# mcu.net
KiCad netlist of a schematic drawn in Altium Designer
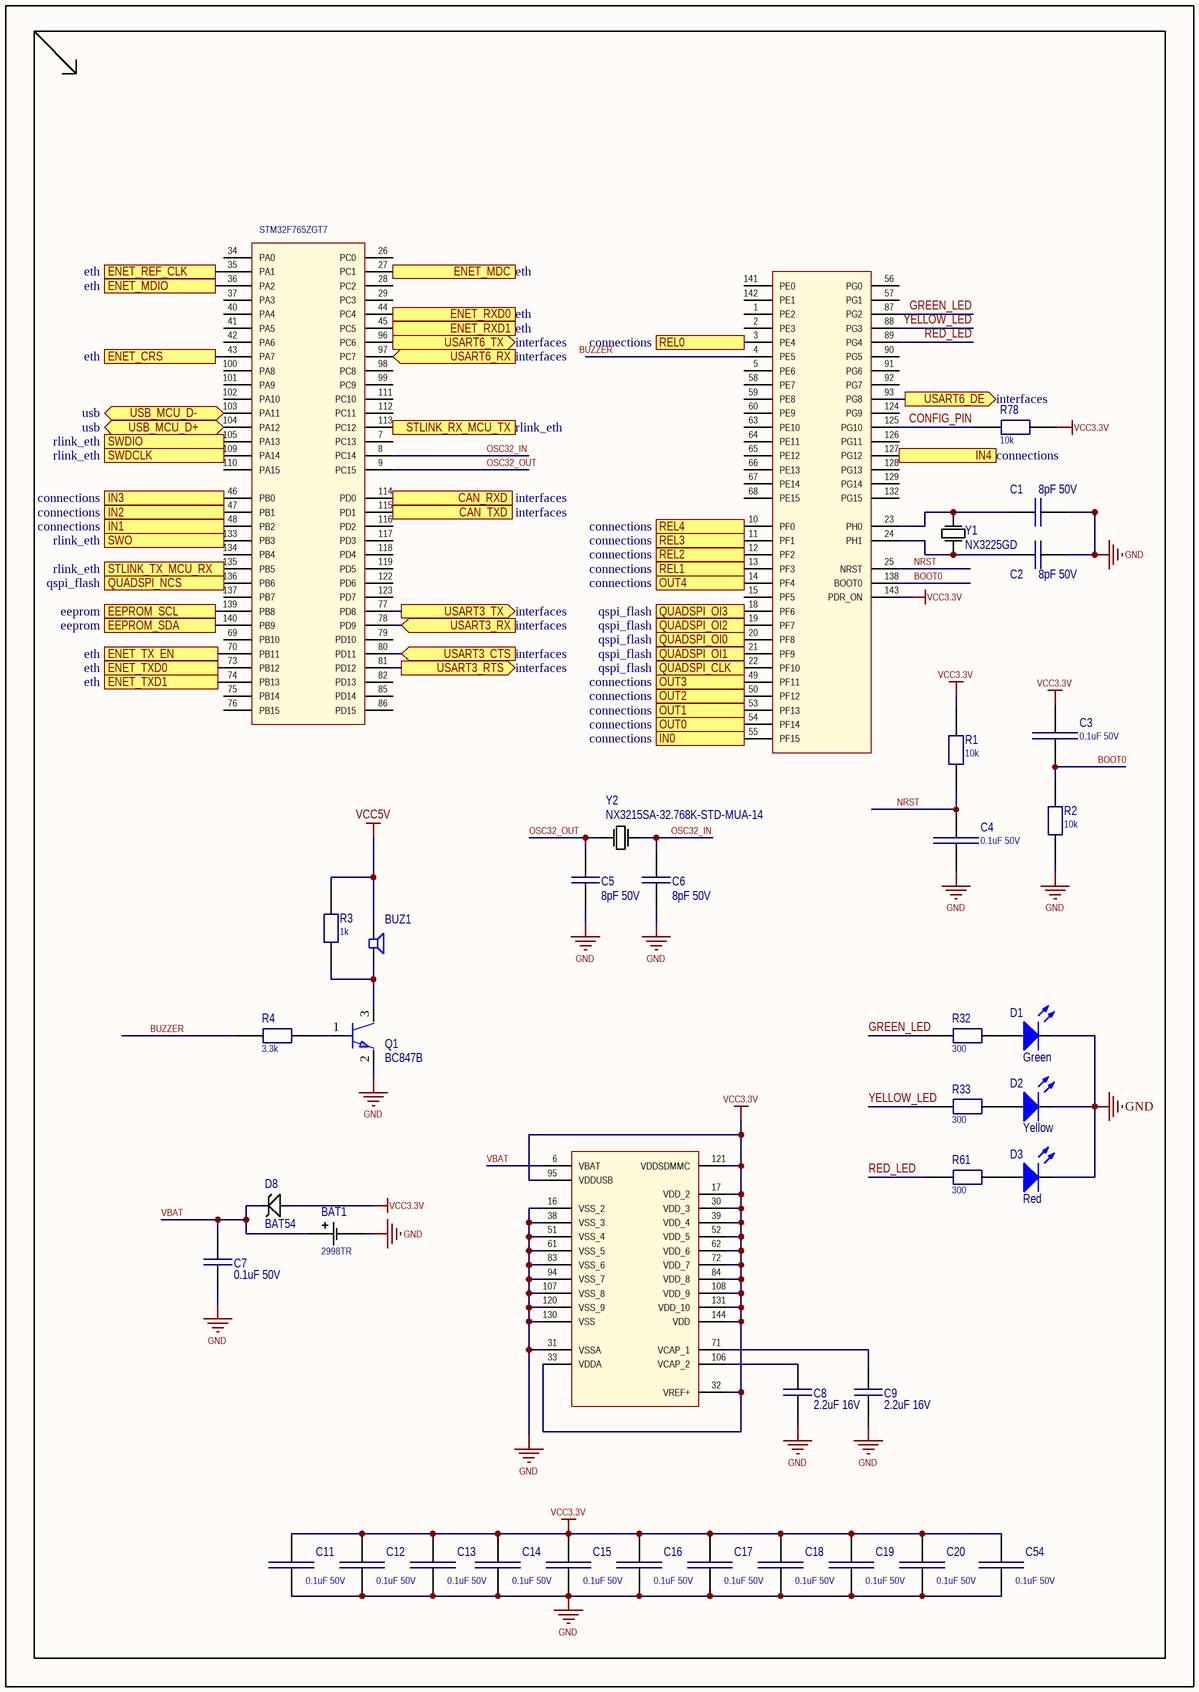
[diagram p0: mcu.SchDoc]

(export (version "E")
  (design (tool "Eeschema 10.0.6"))
  (components
    (comp (ref "BAT1")
      (value "2998TR")
      (footprint "BAT_2998TR")
      (description "Battery")
      (fields (field (name "JLCPCB PART") "C6078169"))
      (libsource (lib "battery_socets") (part "2998TR"))
    )
    (comp (ref "BUZ1")
      (value "~")
      (footprint "SPKR_PKMCS0909E4000-R1")
      (description "Piezoelectric Sounders")
      (fields (field (name "PART") "L-KLS3-SMT-09X1.8") (field (name "ALTERNATIVE PART") "PKMCS0909E4000-R1"))
      (libsource (lib "other") (part "BUZZER"))
    )
    (comp (ref "C1")
      (value "8pF 50V")
      (footprint "C_0603")
      (description "Capacitor")
      (fields (field (name "PART") "CC0603DRNPO9BN8R0") (field (name "JLCPCB PART") "C326970"))
      (libsource (lib "capacitors") (part "CAP_SMD"))
    )
    (comp (ref "C2")
      (value "8pF 50V")
      (footprint "C_0603")
      (description "Capacitor")
      (fields (field (name "PART") "CC0603DRNPO9BN8R0") (field (name "JLCPCB PART") "C326970"))
      (libsource (lib "capacitors") (part "CAP_SMD"))
    )
    (comp (ref "C3")
      (value "0.1uF 50V")
      (footprint "C_0603")
      (description "Capacitor")
      (fields (field (name "PART") "CC0603KPX7R9BB104") (field (name "JLCPCB PART") "C14663"))
      (libsource (lib "AX_Altium_v2.3") (part "C0603"))
    )
    (comp (ref "C4")
      (value "0.1uF 50V")
      (footprint "C_0603")
      (description "Capacitor")
      (fields (field (name "PART") "CC0603KPX7R9BB104") (field (name "JLCPCB PART") "C14663"))
      (libsource (lib "AX_Altium_v2.3") (part "C0603"))
    )
    (comp (ref "C5")
      (value "8pF 50V")
      (footprint "C_0603")
      (description "Capacitor")
      (fields (field (name "PART") "CC0603DRNPO9BN8R0") (field (name "JLCPCB PART") "C326970"))
      (libsource (lib "capacitors") (part "CAP_SMD"))
    )
    (comp (ref "C6")
      (value "8pF 50V")
      (footprint "C_0603")
      (description "Capacitor")
      (fields (field (name "PART") "CC0603DRNPO9BN8R0") (field (name "JLCPCB PART") "C326970"))
      (libsource (lib "capacitors") (part "CAP_SMD"))
    )
    (comp (ref "C7")
      (value "0.1uF 50V")
      (footprint "C_0603")
      (description "Capacitor")
      (fields (field (name "PART") "CC0603KPX7R9BB104") (field (name "JLCPCB PART") "C14663"))
      (libsource (lib "capacitors") (part "CAP_SMD"))
    )
    (comp (ref "C8")
      (value "2.2uF 16V")
      (footprint "C_0603")
      (description "Capacitor")
      (fields (field (name "PART") "CC0603KRX5R7BB225") (field (name "JLCPCB PART") "C106853"))
      (libsource (lib "capacitors") (part "CAP_SMD"))
    )
    (comp (ref "C9")
      (value "2.2uF 16V")
      (footprint "C_0603")
      (description "Capacitor")
      (fields (field (name "PART") "CC0603KRX5R7BB225") (field (name "JLCPCB PART") "C106853"))
      (libsource (lib "capacitors") (part "CAP_SMD"))
    )
    (comp (ref "C11")
      (value "0.1uF 50V")
      (footprint "C_0603")
      (description "Capacitor")
      (fields (field (name "PART") "CC0603KPX7R9BB104") (field (name "JLCPCB PART") "C14663"))
      (libsource (lib "AX_Altium_v2.3") (part "C0603"))
    )
    (comp (ref "C12")
      (value "0.1uF 50V")
      (footprint "C_0603")
      (description "Capacitor")
      (fields (field (name "PART") "CC0603KPX7R9BB104") (field (name "JLCPCB PART") "C14663"))
      (libsource (lib "AX_Altium_v2.3") (part "C0603"))
    )
    (comp (ref "C13")
      (value "0.1uF 50V")
      (footprint "C_0603")
      (description "Capacitor")
      (fields (field (name "PART") "CC0603KPX7R9BB104") (field (name "JLCPCB PART") "C14663"))
      (libsource (lib "AX_Altium_v2.3") (part "C0603"))
    )
    (comp (ref "C14")
      (value "0.1uF 50V")
      (footprint "C_0603")
      (description "Capacitor")
      (fields (field (name "PART") "CC0603KPX7R9BB104") (field (name "JLCPCB PART") "C14663"))
      (libsource (lib "AX_Altium_v2.3") (part "C0603"))
    )
    (comp (ref "C15")
      (value "0.1uF 50V")
      (footprint "C_0603")
      (description "Capacitor")
      (fields (field (name "PART") "CC0603KPX7R9BB104") (field (name "JLCPCB PART") "C14663"))
      (libsource (lib "AX_Altium_v2.3") (part "C0603"))
    )
    (comp (ref "C16")
      (value "0.1uF 50V")
      (footprint "C_0603")
      (description "Capacitor")
      (fields (field (name "PART") "CC0603KPX7R9BB104") (field (name "JLCPCB PART") "C14663"))
      (libsource (lib "AX_Altium_v2.3") (part "C0603"))
    )
    (comp (ref "C17")
      (value "0.1uF 50V")
      (footprint "C_0603")
      (description "Capacitor")
      (fields (field (name "PART") "CC0603KPX7R9BB104") (field (name "JLCPCB PART") "C14663"))
      (libsource (lib "AX_Altium_v2.3") (part "C0603"))
    )
    (comp (ref "C18")
      (value "0.1uF 50V")
      (footprint "C_0603")
      (description "Capacitor")
      (fields (field (name "PART") "CC0603KPX7R9BB104") (field (name "JLCPCB PART") "C14663"))
      (libsource (lib "AX_Altium_v2.3") (part "C0603"))
    )
    (comp (ref "C19")
      (value "0.1uF 50V")
      (footprint "C_0603")
      (description "Capacitor")
      (fields (field (name "PART") "CC0603KPX7R9BB104") (field (name "JLCPCB PART") "C14663"))
      (libsource (lib "AX_Altium_v2.3") (part "C0603"))
    )
    (comp (ref "C20")
      (value "0.1uF 50V")
      (footprint "C_0603")
      (description "Capacitor")
      (fields (field (name "PART") "CC0603KPX7R9BB104") (field (name "JLCPCB PART") "C14663"))
      (libsource (lib "AX_Altium_v2.3") (part "C0603"))
    )
    (comp (ref "C54")
      (value "0.1uF 50V")
      (footprint "C_0603")
      (description "Capacitor")
      (fields (field (name "PART") "CC0603KPX7R9BB104") (field (name "JLCPCB PART") "C14663"))
      (libsource (lib "AX_Altium_v2.3") (part "C0603"))
    )
    (comp (ref "D1")
      (value "Green")
      (footprint "LED_0603")
      (description "LED")
      (fields (field (name "PART") "FYLS-0603PGC") (field (name "ALTERNATIVE PART") "KP-1608CGCK"))
      (libsource (lib "led_lcd") (part "LED_SMT_0603"))
    )
    (comp (ref "D2")
      (value "Yellow")
      (footprint "LED_0603")
      (description "LED")
      (fields (field (name "PART") "FYLS-0603PGC") (field (name "ALTERNATIVE PART") "KP-1608CGCK"))
      (libsource (lib "led_lcd") (part "LED_SMT_0603"))
    )
    (comp (ref "D3")
      (value "Red")
      (footprint "LED_0603")
      (description "LED")
      (fields (field (name "PART") "FYLS-0603PGC") (field (name "ALTERNATIVE PART") "KP-1608CGCK"))
      (libsource (lib "led_lcd") (part "LED_SMT_0603"))
    )
    (comp (ref "D8")
      (value "BAT54")
      (footprint "SOT23")
      (description "Diode")
      (fields (field (name "JLCPCB PART") "C408389"))
      (libsource (lib "diode") (part "BAT54"))
    )
    (comp (ref "Q1")
      (value "BC847B")
      (footprint "SOT23")
      (description "Transistor")
      (fields (field (name "JLCPCB PART") "C181140"))
      (libsource (lib "AX_Altium_v2.3") (part "BC847B"))
    )
    (comp (ref "R1")
      (value "10k")
      (footprint "R_0603")
      (description "Resistor")
      (fields (field (name "PART") "RC0603JR-0710KL") (field (name "JLCPCB PART") "C99198"))
      (libsource (lib "resistors") (part "RES_SMD"))
    )
    (comp (ref "R2")
      (value "10k")
      (footprint "R_0603")
      (description "Resistor")
      (fields (field (name "PART") "RC0603JR-0710KL") (field (name "JLCPCB PART") "C99198"))
      (libsource (lib "resistors") (part "RES_SMD"))
    )
    (comp (ref "R3")
      (value "1k")
      (footprint "R_0603")
      (description "Resistor")
      (fields (field (name "PART") "RC0603FR-071KL") (field (name "JLCPCB PART") "C22548"))
      (libsource (lib "resistors") (part "RES_SMD"))
    )
    (comp (ref "R4")
      (value "3.3k")
      (footprint "R_0603")
      (description "Resistor")
      (fields (field (name "PART") "RC0603FR-073K3L") (field (name "JLCPCB PART") "C108078"))
      (libsource (lib "resistors") (part "RES_SMD"))
    )
    (comp (ref "R32")
      (value "300")
      (footprint "R_0603")
      (description "Resistor")
      (fields (field (name "PART") "RC0603FR-07300RL") (field (name "JLCPCB PART") "C114617"))
      (libsource (lib "resistors") (part "R0603"))
    )
    (comp (ref "R33")
      (value "300")
      (footprint "R_0603")
      (description "Resistor")
      (fields (field (name "PART") "RC0603FR-07300RL") (field (name "JLCPCB PART") "C114617"))
      (libsource (lib "resistors") (part "R0603"))
    )
    (comp (ref "R61")
      (value "300")
      (footprint "R_0603")
      (description "Resistor")
      (fields (field (name "PART") "RC0603FR-07300RL") (field (name "JLCPCB PART") "C114617"))
      (libsource (lib "resistors") (part "R0603"))
    )
    (comp (ref "R78")
      (value "10k")
      (footprint "R_0603")
      (description "Resistor")
      (fields (field (name "PART") "RC0603JR-0710KL") (field (name "JLCPCB PART") "C99198"))
      (libsource (lib "resistors") (part "RES_SMD"))
    )
    (comp (ref "U1")
      (value "STM32F765ZGT7")
      (footprint "TQFP144_M")
      (description "Microcontroller")
      (fields
        (field (name "MANUFACTURER_PART_NUMBER") "STM32F76XZXT")
        (field (name "PART") "STM32F765ZGT")
        (field (name "COPYRIGHT") "Copyright (C) 2016 Accelerated Designs. All rights reserved")
      )
      (libsource (lib "STM32 F4") (part "STM32F76XZXT"))
    )
    (comp (ref "Y1")
      (value "NX3225GD")
      (footprint "NX3225GD")
      (description "Crystal Oscillator")
      (fields (field (name "PART") "NX3225GD-8MHZ-STD-CRA-3") (field (name "JLCPCB PART") "C889706"))
      (libsource (lib "crystals_oscillators") (part "NX3225GD"))
    )
    (comp (ref "Y2")
      (value "NX3215SA-32.768K-STD-MUA-14")
      (footprint "XTAL_NX3215SA-32.768K-STD-MUA-8")
      (description "Crystal Oscillator")
      (fields (field (name "JLCPCB PART") "C156244"))
      (libsource (lib "crystals_oscillators") (part "NX3215SA-32.768K"))
    )
  )
  (nets
    (net (code "1") (name "/BOOT0") (class "Default")
      (node (ref "C3") (pin "2") (pinfunction "2_2") (pintype "passive"))
      (node (ref "R2") (pin "2") (pinfunction "2_2") (pintype "passive"))
      (node (ref "U1") (pin "138") (pinfunction "BOOT0_138") (pintype "passive"))
    )
    (net (code "2") (name "/BUZZER") (class "Default")
      (node (ref "R4") (pin "1") (pinfunction "1_1") (pintype "passive"))
      (node (ref "U1") (pin "4") (pinfunction "PE5_4") (pintype "passive"))
    )
    (net (code "3") (name "/CAN_RXD") (class "Default")
      (node (ref "U1") (pin "114") (pinfunction "PD0_114") (pintype "passive"))
    )
    (net (code "4") (name "/CAN_TXD") (class "Default")
      (node (ref "U1") (pin "115") (pinfunction "PD1_115") (pintype "passive"))
    )
    (net (code "5") (name "/CONFIG_PIN") (class "Default")
      (node (ref "R78") (pin "1") (pinfunction "1_1") (pintype "passive"))
      (node (ref "U1") (pin "125") (pinfunction "PG10_125") (pintype "passive"))
    )
    (net (code "6") (name "/EEPROM_SCL") (class "Default")
      (node (ref "U1") (pin "139") (pinfunction "PB8_139") (pintype "passive"))
    )
    (net (code "7") (name "/EEPROM_SDA") (class "Default")
      (node (ref "U1") (pin "140") (pinfunction "PB9_140") (pintype "passive"))
    )
    (net (code "8") (name "/ENET_CRS") (class "Default")
      (node (ref "U1") (pin "43") (pinfunction "PA7_43") (pintype "passive"))
    )
    (net (code "9") (name "/ENET_MDC") (class "Default")
      (node (ref "U1") (pin "27") (pinfunction "PC1_27") (pintype "passive"))
    )
    (net (code "10") (name "/ENET_MDIO") (class "Default")
      (node (ref "U1") (pin "36") (pinfunction "PA2_36") (pintype "passive"))
    )
    (net (code "11") (name "/ENET_REF_CLK") (class "Default")
      (node (ref "U1") (pin "35") (pinfunction "PA1_35") (pintype "passive"))
    )
    (net (code "12") (name "/ENET_RXD0") (class "Default")
      (node (ref "U1") (pin "44") (pinfunction "PC4_44") (pintype "passive"))
    )
    (net (code "13") (name "/ENET_RXD1") (class "Default")
      (node (ref "U1") (pin "45") (pinfunction "PC5_45") (pintype "passive"))
    )
    (net (code "14") (name "/ENET_TXD0") (class "Default")
      (node (ref "U1") (pin "73") (pinfunction "PB12_73") (pintype "passive"))
    )
    (net (code "15") (name "/ENET_TXD1") (class "Default")
      (node (ref "U1") (pin "74") (pinfunction "PB13_74") (pintype "passive"))
    )
    (net (code "16") (name "/ENET_TX_EN") (class "Default")
      (node (ref "U1") (pin "70") (pinfunction "PB11_70") (pintype "passive"))
    )
    (net (code "17") (name "/GREEN_LED") (class "Default")
      (node (ref "R32") (pin "2") (pinfunction "2_2") (pintype "passive"))
      (node (ref "U1") (pin "87") (pinfunction "PG2_87") (pintype "passive"))
    )
    (net (code "18") (name "/IN0") (class "Default")
      (node (ref "U1") (pin "55") (pinfunction "PF15_55") (pintype "passive"))
    )
    (net (code "19") (name "/IN1") (class "Default")
      (node (ref "U1") (pin "48") (pinfunction "PB2_48") (pintype "passive"))
    )
    (net (code "20") (name "/IN2") (class "Default")
      (node (ref "U1") (pin "47") (pinfunction "PB1_47") (pintype "passive"))
    )
    (net (code "21") (name "/IN3") (class "Default")
      (node (ref "U1") (pin "46") (pinfunction "PB0_46") (pintype "passive"))
    )
    (net (code "22") (name "/IN4") (class "Default")
      (node (ref "U1") (pin "127") (pinfunction "PG12_127") (pintype "passive"))
    )
    (net (code "23") (name "/NRST") (class "Default")
      (node (ref "C4") (pin "2") (pinfunction "2_2") (pintype "passive"))
      (node (ref "R1") (pin "1") (pinfunction "1_1") (pintype "passive"))
      (node (ref "U1") (pin "25") (pinfunction "NRST_25") (pintype "passive"))
    )
    (net (code "24") (name "/OSC32_IN") (class "Default")
      (node (ref "C6") (pin "2") (pinfunction "2_2") (pintype "passive"))
      (node (ref "U1") (pin "8") (pinfunction "PC14_8") (pintype "passive"))
      (node (ref "Y2") (pin "2") (pinfunction "OSC2_2") (pintype "passive"))
    )
    (net (code "25") (name "/OSC32_OUT") (class "Default")
      (node (ref "C5") (pin "2") (pinfunction "2_2") (pintype "passive"))
      (node (ref "U1") (pin "9") (pinfunction "PC15_9") (pintype "passive"))
      (node (ref "Y2") (pin "1") (pinfunction "OSC1_1") (pintype "passive"))
    )
    (net (code "26") (name "/OUT0") (class "Default")
      (node (ref "U1") (pin "54") (pinfunction "PF14_54") (pintype "passive"))
    )
    (net (code "27") (name "/OUT1") (class "Default")
      (node (ref "U1") (pin "53") (pinfunction "PF13_53") (pintype "passive"))
    )
    (net (code "28") (name "/OUT2") (class "Default")
      (node (ref "U1") (pin "50") (pinfunction "PF12_50") (pintype "passive"))
    )
    (net (code "29") (name "/OUT3") (class "Default")
      (node (ref "U1") (pin "49") (pinfunction "PF11_49") (pintype "passive"))
    )
    (net (code "30") (name "/OUT4") (class "Default")
      (node (ref "U1") (pin "14") (pinfunction "PF4_14") (pintype "passive"))
    )
    (net (code "31") (name "/QUADSPI_CLK") (class "Default")
      (node (ref "U1") (pin "22") (pinfunction "PF10_22") (pintype "passive"))
    )
    (net (code "32") (name "/QUADSPI_NCS") (class "Default")
      (node (ref "U1") (pin "136") (pinfunction "PB6_136") (pintype "passive"))
    )
    (net (code "33") (name "/QUADSPI_OI0") (class "Default")
      (node (ref "U1") (pin "20") (pinfunction "PF8_20") (pintype "passive"))
    )
    (net (code "34") (name "/QUADSPI_OI1") (class "Default")
      (node (ref "U1") (pin "21") (pinfunction "PF9_21") (pintype "passive"))
    )
    (net (code "35") (name "/QUADSPI_OI2") (class "Default")
      (node (ref "U1") (pin "19") (pinfunction "PF7_19") (pintype "passive"))
    )
    (net (code "36") (name "/QUADSPI_OI3") (class "Default")
      (node (ref "U1") (pin "18") (pinfunction "PF6_18") (pintype "passive"))
    )
    (net (code "37") (name "/RED_LED") (class "Default")
      (node (ref "R61") (pin "2") (pinfunction "2_2") (pintype "passive"))
      (node (ref "U1") (pin "89") (pinfunction "PG4_89") (pintype "passive"))
    )
    (net (code "38") (name "/REL0") (class "Default")
      (node (ref "U1") (pin "3") (pinfunction "PE4_3") (pintype "passive"))
    )
    (net (code "39") (name "/REL1") (class "Default")
      (node (ref "U1") (pin "13") (pinfunction "PF3_13") (pintype "passive"))
    )
    (net (code "40") (name "/REL2") (class "Default")
      (node (ref "U1") (pin "12") (pinfunction "PF2_12") (pintype "passive"))
    )
    (net (code "41") (name "/REL3") (class "Default")
      (node (ref "U1") (pin "11") (pinfunction "PF1_11") (pintype "passive"))
    )
    (net (code "42") (name "/REL4") (class "Default")
      (node (ref "U1") (pin "10") (pinfunction "PF0_10") (pintype "passive"))
    )
    (net (code "43") (name "/STLINK_RX_MCU_TX") (class "Default")
      (node (ref "U1") (pin "113") (pinfunction "PC12_113") (pintype "passive"))
    )
    (net (code "44") (name "/STLINK_TX_MCU_RX") (class "Default")
      (node (ref "U1") (pin "135") (pinfunction "PB5_135") (pintype "passive"))
    )
    (net (code "45") (name "/SWDCLK") (class "Default")
      (node (ref "U1") (pin "109") (pinfunction "PA14_109") (pintype "passive"))
    )
    (net (code "46") (name "/SWDIO") (class "Default")
      (node (ref "U1") (pin "105") (pinfunction "PA13_105") (pintype "passive"))
    )
    (net (code "47") (name "/SWO") (class "Default")
      (node (ref "U1") (pin "133") (pinfunction "PB3_133") (pintype "passive"))
    )
    (net (code "48") (name "/USART3_CTS") (class "Default")
      (node (ref "U1") (pin "80") (pinfunction "PD11_80") (pintype "passive"))
    )
    (net (code "49") (name "/USART3_RTS") (class "Default")
      (node (ref "U1") (pin "81") (pinfunction "PD12_81") (pintype "passive"))
    )
    (net (code "50") (name "/USART3_RX") (class "Default")
      (node (ref "U1") (pin "78") (pinfunction "PD9_78") (pintype "passive"))
    )
    (net (code "51") (name "/USART3_TX") (class "Default")
      (node (ref "U1") (pin "77") (pinfunction "PD8_77") (pintype "passive"))
    )
    (net (code "52") (name "/USART6_DE") (class "Default")
      (node (ref "U1") (pin "93") (pinfunction "PG8_93") (pintype "passive"))
    )
    (net (code "53") (name "/USART6_RX") (class "Default")
      (node (ref "U1") (pin "97") (pinfunction "PC7_97") (pintype "passive"))
    )
    (net (code "54") (name "/USART6_TX") (class "Default")
      (node (ref "U1") (pin "96") (pinfunction "PC6_96") (pintype "passive"))
    )
    (net (code "55") (name "/USB_MCU_D+") (class "Default")
      (node (ref "U1") (pin "104") (pinfunction "PA12_104") (pintype "passive"))
    )
    (net (code "56") (name "/USB_MCU_D-") (class "Default")
      (node (ref "U1") (pin "103") (pinfunction "PA11_103") (pintype "passive"))
    )
    (net (code "57") (name "/VBAT") (class "Default")
      (node (ref "BAT1") (pin "P1") (pinfunction "+_P1") (pintype "passive"))
      (node (ref "C7") (pin "2") (pinfunction "2_2") (pintype "passive"))
      (node (ref "D8") (pin "3") (pinfunction "3_3") (pintype "passive"))
      (node (ref "U1") (pin "6") (pinfunction "VBAT_6") (pintype "passive"))
    )
    (net (code "58") (name "/YELLOW_LED") (class "Default")
      (node (ref "R33") (pin "2") (pinfunction "2_2") (pintype "passive"))
      (node (ref "U1") (pin "88") (pinfunction "PG3_88") (pintype "passive"))
    )
    (net (code "59") (name "GND") (class "Default")
      (node (ref "BAT1") (pin "N") (pinfunction "-_N") (pintype "passive"))
      (node (ref "C1") (pin "1") (pinfunction "1_1") (pintype "passive"))
      (node (ref "C11") (pin "1") (pinfunction "1_1") (pintype "passive"))
      (node (ref "C12") (pin "1") (pinfunction "1_1") (pintype "passive"))
      (node (ref "C13") (pin "1") (pinfunction "1_1") (pintype "passive"))
      (node (ref "C14") (pin "1") (pinfunction "1_1") (pintype "passive"))
      (node (ref "C15") (pin "1") (pinfunction "1_1") (pintype "passive"))
      (node (ref "C16") (pin "1") (pinfunction "1_1") (pintype "passive"))
      (node (ref "C17") (pin "1") (pinfunction "1_1") (pintype "passive"))
      (node (ref "C18") (pin "1") (pinfunction "1_1") (pintype "passive"))
      (node (ref "C19") (pin "1") (pinfunction "1_1") (pintype "passive"))
      (node (ref "C2") (pin "1") (pinfunction "1_1") (pintype "passive"))
      (node (ref "C20") (pin "1") (pinfunction "1_1") (pintype "passive"))
      (node (ref "C4") (pin "1") (pinfunction "1_1") (pintype "passive"))
      (node (ref "C5") (pin "1") (pinfunction "1_1") (pintype "passive"))
      (node (ref "C54") (pin "1") (pinfunction "1_1") (pintype "passive"))
      (node (ref "C6") (pin "1") (pinfunction "1_1") (pintype "passive"))
      (node (ref "C7") (pin "1") (pinfunction "1_1") (pintype "passive"))
      (node (ref "C8") (pin "1") (pinfunction "1_1") (pintype "passive"))
      (node (ref "C9") (pin "1") (pinfunction "1_1") (pintype "passive"))
      (node (ref "D1") (pin "2") (pinfunction "K_2") (pintype "passive"))
      (node (ref "D2") (pin "2") (pinfunction "K_2") (pintype "passive"))
      (node (ref "D3") (pin "2") (pinfunction "K_2") (pintype "passive"))
      (node (ref "Q1") (pin "2") (pintype "passive"))
      (node (ref "R2") (pin "1") (pinfunction "1_1") (pintype "passive"))
      (node (ref "U1") (pin "107") (pinfunction "VSS_8_107") (pintype "passive"))
      (node (ref "U1") (pin "120") (pinfunction "VSS_9_120") (pintype "passive"))
      (node (ref "U1") (pin "130") (pinfunction "VSS_130") (pintype "passive"))
      (node (ref "U1") (pin "16") (pinfunction "VSS_2_16") (pintype "passive"))
      (node (ref "U1") (pin "31") (pinfunction "VSSA_31") (pintype "passive"))
      (node (ref "U1") (pin "38") (pinfunction "VSS_3_38") (pintype "passive"))
      (node (ref "U1") (pin "51") (pinfunction "VSS_4_51") (pintype "passive"))
      (node (ref "U1") (pin "61") (pinfunction "VSS_5_61") (pintype "passive"))
      (node (ref "U1") (pin "83") (pinfunction "VSS_6_83") (pintype "passive"))
      (node (ref "U1") (pin "94") (pinfunction "VSS_7_94") (pintype "passive"))
    )
    (net (code "60") (name "Net-(BUZ1-Pad2)") (class "Default")
      (node (ref "BUZ1") (pin "2") (pinfunction "2_2") (pintype "passive"))
      (node (ref "Q1") (pin "3") (pintype "passive"))
      (node (ref "R3") (pin "1") (pinfunction "1_1") (pintype "passive"))
    )
    (net (code "61") (name "Net-(D1-A)") (class "Default")
      (node (ref "D1") (pin "1") (pinfunction "A_1") (pintype "passive"))
      (node (ref "R32") (pin "1") (pinfunction "1_1") (pintype "passive"))
    )
    (net (code "62") (name "Net-(D2-A)") (class "Default")
      (node (ref "D2") (pin "1") (pinfunction "A_1") (pintype "passive"))
      (node (ref "R33") (pin "1") (pinfunction "1_1") (pintype "passive"))
    )
    (net (code "63") (name "Net-(D3-A)") (class "Default")
      (node (ref "D3") (pin "1") (pinfunction "A_1") (pintype "passive"))
      (node (ref "R61") (pin "1") (pinfunction "1_1") (pintype "passive"))
    )
    (net (code "64") (name "Net-(Q1-Pad1)") (class "Default")
      (node (ref "Q1") (pin "1") (pintype "passive"))
      (node (ref "R4") (pin "2") (pinfunction "2_2") (pintype "passive"))
    )
    (net (code "65") (name "Net-(U1B-PH0)") (class "Default")
      (node (ref "C1") (pin "2") (pinfunction "2_2") (pintype "passive"))
      (node (ref "U1") (pin "23") (pinfunction "PH0_23") (pintype "passive"))
      (node (ref "Y1") (pin "2") (pinfunction "OSC2_2") (pintype "passive"))
    )
    (net (code "66") (name "Net-(U1B-PH1)") (class "Default")
      (node (ref "C2") (pin "2") (pinfunction "2_2") (pintype "passive"))
      (node (ref "U1") (pin "24") (pinfunction "PH1_24") (pintype "passive"))
      (node (ref "Y1") (pin "1") (pinfunction "OSC1_1") (pintype "passive"))
    )
    (net (code "67") (name "Net-(U1C-VCAP_1)") (class "Default")
      (node (ref "C9") (pin "2") (pinfunction "2_2") (pintype "passive"))
      (node (ref "U1") (pin "71") (pinfunction "VCAP_1_71") (pintype "passive"))
    )
    (net (code "68") (name "Net-(U1C-VCAP_2)") (class "Default")
      (node (ref "C8") (pin "2") (pinfunction "2_2") (pintype "passive"))
      (node (ref "U1") (pin "106") (pinfunction "VCAP_2_106") (pintype "passive"))
    )
    (net (code "69") (name "VCC3.3V") (class "Default")
      (node (ref "C11") (pin "2") (pinfunction "2_2") (pintype "passive"))
      (node (ref "C12") (pin "2") (pinfunction "2_2") (pintype "passive"))
      (node (ref "C13") (pin "2") (pinfunction "2_2") (pintype "passive"))
      (node (ref "C14") (pin "2") (pinfunction "2_2") (pintype "passive"))
      (node (ref "C15") (pin "2") (pinfunction "2_2") (pintype "passive"))
      (node (ref "C16") (pin "2") (pinfunction "2_2") (pintype "passive"))
      (node (ref "C17") (pin "2") (pinfunction "2_2") (pintype "passive"))
      (node (ref "C18") (pin "2") (pinfunction "2_2") (pintype "passive"))
      (node (ref "C19") (pin "2") (pinfunction "2_2") (pintype "passive"))
      (node (ref "C20") (pin "2") (pinfunction "2_2") (pintype "passive"))
      (node (ref "C3") (pin "1") (pinfunction "1_1") (pintype "passive"))
      (node (ref "C54") (pin "2") (pinfunction "2_2") (pintype "passive"))
      (node (ref "D8") (pin "1") (pinfunction "1_1") (pintype "passive"))
      (node (ref "R1") (pin "2") (pinfunction "2_2") (pintype "passive"))
      (node (ref "R78") (pin "2") (pinfunction "2_2") (pintype "passive"))
      (node (ref "U1") (pin "108") (pinfunction "VDD_9_108") (pintype "passive"))
      (node (ref "U1") (pin "121") (pinfunction "VDDSDMMC_121") (pintype "passive"))
      (node (ref "U1") (pin "131") (pinfunction "VDD_10_131") (pintype "passive"))
      (node (ref "U1") (pin "143") (pinfunction "PDR_ON_143") (pintype "passive"))
      (node (ref "U1") (pin "144") (pinfunction "VDD_144") (pintype "passive"))
      (node (ref "U1") (pin "17") (pinfunction "VDD_2_17") (pintype "passive"))
      (node (ref "U1") (pin "30") (pinfunction "VDD_3_30") (pintype "passive"))
      (node (ref "U1") (pin "32") (pinfunction "VREF+_32") (pintype "passive"))
      (node (ref "U1") (pin "33") (pinfunction "VDDA_33") (pintype "passive"))
      (node (ref "U1") (pin "39") (pinfunction "VDD_4_39") (pintype "passive"))
      (node (ref "U1") (pin "52") (pinfunction "VDD_5_52") (pintype "passive"))
      (node (ref "U1") (pin "62") (pinfunction "VDD_6_62") (pintype "passive"))
      (node (ref "U1") (pin "72") (pinfunction "VDD_7_72") (pintype "passive"))
      (node (ref "U1") (pin "84") (pinfunction "VDD_8_84") (pintype "passive"))
      (node (ref "U1") (pin "95") (pinfunction "VDDUSB_95") (pintype "passive"))
    )
    (net (code "70") (name "VCC5V") (class "Default")
      (node (ref "BUZ1") (pin "1") (pinfunction "1_1") (pintype "passive"))
      (node (ref "R3") (pin "2") (pinfunction "2_2") (pintype "passive"))
    )
    (net (code "71") (name "unconnected-(U1A-PA0-Pad34)") (class "Default")
      (node (ref "U1") (pin "34") (pinfunction "PA0_34") (pintype "passive"))
    )
    (net (code "72") (name "unconnected-(U1A-PA3-Pad37)") (class "Default")
      (node (ref "U1") (pin "37") (pinfunction "PA3_37") (pintype "passive"))
    )
    (net (code "73") (name "unconnected-(U1A-PA4-Pad40)") (class "Default")
      (node (ref "U1") (pin "40") (pinfunction "PA4_40") (pintype "passive"))
    )
    (net (code "74") (name "unconnected-(U1A-PA5-Pad41)") (class "Default")
      (node (ref "U1") (pin "41") (pinfunction "PA5_41") (pintype "passive"))
    )
    (net (code "75") (name "unconnected-(U1A-PA6-Pad42)") (class "Default")
      (node (ref "U1") (pin "42") (pinfunction "PA6_42") (pintype "passive"))
    )
    (net (code "76") (name "unconnected-(U1A-PA8-Pad100)") (class "Default")
      (node (ref "U1") (pin "100") (pinfunction "PA8_100") (pintype "passive"))
    )
    (net (code "77") (name "unconnected-(U1A-PA9-Pad101)") (class "Default")
      (node (ref "U1") (pin "101") (pinfunction "PA9_101") (pintype "passive"))
    )
    (net (code "78") (name "unconnected-(U1A-PA10-Pad102)") (class "Default")
      (node (ref "U1") (pin "102") (pinfunction "PA10_102") (pintype "passive"))
    )
    (net (code "79") (name "unconnected-(U1A-PA15-Pad110)") (class "Default")
      (node (ref "U1") (pin "110") (pinfunction "PA15_110") (pintype "passive"))
    )
    (net (code "80") (name "unconnected-(U1A-PB4-Pad134)") (class "Default")
      (node (ref "U1") (pin "134") (pinfunction "PB4_134") (pintype "passive"))
    )
    (net (code "81") (name "unconnected-(U1A-PB7-Pad137)") (class "Default")
      (node (ref "U1") (pin "137") (pinfunction "PB7_137") (pintype "passive"))
    )
    (net (code "82") (name "unconnected-(U1A-PB10-Pad69)") (class "Default")
      (node (ref "U1") (pin "69") (pinfunction "PB10_69") (pintype "passive"))
    )
    (net (code "83") (name "unconnected-(U1A-PB14-Pad75)") (class "Default")
      (node (ref "U1") (pin "75") (pinfunction "PB14_75") (pintype "passive"))
    )
    (net (code "84") (name "unconnected-(U1A-PB15-Pad76)") (class "Default")
      (node (ref "U1") (pin "76") (pinfunction "PB15_76") (pintype "passive"))
    )
    (net (code "85") (name "unconnected-(U1A-PC0-Pad26)") (class "Default")
      (node (ref "U1") (pin "26") (pinfunction "PC0_26") (pintype "passive"))
    )
    (net (code "86") (name "unconnected-(U1A-PC2-Pad28)") (class "Default")
      (node (ref "U1") (pin "28") (pinfunction "PC2_28") (pintype "passive"))
    )
    (net (code "87") (name "unconnected-(U1A-PC3-Pad29)") (class "Default")
      (node (ref "U1") (pin "29") (pinfunction "PC3_29") (pintype "passive"))
    )
    (net (code "88") (name "unconnected-(U1A-PC8-Pad98)") (class "Default")
      (node (ref "U1") (pin "98") (pinfunction "PC8_98") (pintype "passive"))
    )
    (net (code "89") (name "unconnected-(U1A-PC9-Pad99)") (class "Default")
      (node (ref "U1") (pin "99") (pinfunction "PC9_99") (pintype "passive"))
    )
    (net (code "90") (name "unconnected-(U1A-PC10-Pad111)") (class "Default")
      (node (ref "U1") (pin "111") (pinfunction "PC10_111") (pintype "passive"))
    )
    (net (code "91") (name "unconnected-(U1A-PC11-Pad112)") (class "Default")
      (node (ref "U1") (pin "112") (pinfunction "PC11_112") (pintype "passive"))
    )
    (net (code "92") (name "unconnected-(U1A-PC13-Pad7)") (class "Default")
      (node (ref "U1") (pin "7") (pinfunction "PC13_7") (pintype "passive"))
    )
    (net (code "93") (name "unconnected-(U1A-PD2-Pad116)") (class "Default")
      (node (ref "U1") (pin "116") (pinfunction "PD2_116") (pintype "passive"))
    )
    (net (code "94") (name "unconnected-(U1A-PD3-Pad117)") (class "Default")
      (node (ref "U1") (pin "117") (pinfunction "PD3_117") (pintype "passive"))
    )
    (net (code "95") (name "unconnected-(U1A-PD4-Pad118)") (class "Default")
      (node (ref "U1") (pin "118") (pinfunction "PD4_118") (pintype "passive"))
    )
    (net (code "96") (name "unconnected-(U1A-PD5-Pad119)") (class "Default")
      (node (ref "U1") (pin "119") (pinfunction "PD5_119") (pintype "passive"))
    )
    (net (code "97") (name "unconnected-(U1A-PD6-Pad122)") (class "Default")
      (node (ref "U1") (pin "122") (pinfunction "PD6_122") (pintype "passive"))
    )
    (net (code "98") (name "unconnected-(U1A-PD7-Pad123)") (class "Default")
      (node (ref "U1") (pin "123") (pinfunction "PD7_123") (pintype "passive"))
    )
    (net (code "99") (name "unconnected-(U1A-PD10-Pad79)") (class "Default")
      (node (ref "U1") (pin "79") (pinfunction "PD10_79") (pintype "passive"))
    )
    (net (code "100") (name "unconnected-(U1A-PD13-Pad82)") (class "Default")
      (node (ref "U1") (pin "82") (pinfunction "PD13_82") (pintype "passive"))
    )
    (net (code "101") (name "unconnected-(U1A-PD14-Pad85)") (class "Default")
      (node (ref "U1") (pin "85") (pinfunction "PD14_85") (pintype "passive"))
    )
    (net (code "102") (name "unconnected-(U1A-PD15-Pad86)") (class "Default")
      (node (ref "U1") (pin "86") (pinfunction "PD15_86") (pintype "passive"))
    )
    (net (code "103") (name "unconnected-(U1B-PE0-Pad141)") (class "Default")
      (node (ref "U1") (pin "141") (pinfunction "PE0_141") (pintype "passive"))
    )
    (net (code "104") (name "unconnected-(U1B-PE1-Pad142)") (class "Default")
      (node (ref "U1") (pin "142") (pinfunction "PE1_142") (pintype "passive"))
    )
    (net (code "105") (name "unconnected-(U1B-PE2-Pad1)") (class "Default")
      (node (ref "U1") (pin "1") (pinfunction "PE2_1") (pintype "passive"))
    )
    (net (code "106") (name "unconnected-(U1B-PE3-Pad2)") (class "Default")
      (node (ref "U1") (pin "2") (pinfunction "PE3_2") (pintype "passive"))
    )
    (net (code "107") (name "unconnected-(U1B-PE6-Pad5)") (class "Default")
      (node (ref "U1") (pin "5") (pinfunction "PE6_5") (pintype "passive"))
    )
    (net (code "108") (name "unconnected-(U1B-PE7-Pad58)") (class "Default")
      (node (ref "U1") (pin "58") (pinfunction "PE7_58") (pintype "passive"))
    )
    (net (code "109") (name "unconnected-(U1B-PE8-Pad59)") (class "Default")
      (node (ref "U1") (pin "59") (pinfunction "PE8_59") (pintype "passive"))
    )
    (net (code "110") (name "unconnected-(U1B-PE9-Pad60)") (class "Default")
      (node (ref "U1") (pin "60") (pinfunction "PE9_60") (pintype "passive"))
    )
    (net (code "111") (name "unconnected-(U1B-PE10-Pad63)") (class "Default")
      (node (ref "U1") (pin "63") (pinfunction "PE10_63") (pintype "passive"))
    )
    (net (code "112") (name "unconnected-(U1B-PE11-Pad64)") (class "Default")
      (node (ref "U1") (pin "64") (pinfunction "PE11_64") (pintype "passive"))
    )
    (net (code "113") (name "unconnected-(U1B-PE12-Pad65)") (class "Default")
      (node (ref "U1") (pin "65") (pinfunction "PE12_65") (pintype "passive"))
    )
    (net (code "114") (name "unconnected-(U1B-PE13-Pad66)") (class "Default")
      (node (ref "U1") (pin "66") (pinfunction "PE13_66") (pintype "passive"))
    )
    (net (code "115") (name "unconnected-(U1B-PE14-Pad67)") (class "Default")
      (node (ref "U1") (pin "67") (pinfunction "PE14_67") (pintype "passive"))
    )
    (net (code "116") (name "unconnected-(U1B-PE15-Pad68)") (class "Default")
      (node (ref "U1") (pin "68") (pinfunction "PE15_68") (pintype "passive"))
    )
    (net (code "117") (name "unconnected-(U1B-PF5-Pad15)") (class "Default")
      (node (ref "U1") (pin "15") (pinfunction "PF5_15") (pintype "passive"))
    )
    (net (code "118") (name "unconnected-(U1B-PG0-Pad56)") (class "Default")
      (node (ref "U1") (pin "56") (pinfunction "PG0_56") (pintype "passive"))
    )
    (net (code "119") (name "unconnected-(U1B-PG1-Pad57)") (class "Default")
      (node (ref "U1") (pin "57") (pinfunction "PG1_57") (pintype "passive"))
    )
    (net (code "120") (name "unconnected-(U1B-PG5-Pad90)") (class "Default")
      (node (ref "U1") (pin "90") (pinfunction "PG5_90") (pintype "passive"))
    )
    (net (code "121") (name "unconnected-(U1B-PG6-Pad91)") (class "Default")
      (node (ref "U1") (pin "91") (pinfunction "PG6_91") (pintype "passive"))
    )
    (net (code "122") (name "unconnected-(U1B-PG7-Pad92)") (class "Default")
      (node (ref "U1") (pin "92") (pinfunction "PG7_92") (pintype "passive"))
    )
    (net (code "123") (name "unconnected-(U1B-PG9-Pad124)") (class "Default")
      (node (ref "U1") (pin "124") (pinfunction "PG9_124") (pintype "passive"))
    )
    (net (code "124") (name "unconnected-(U1B-PG11-Pad126)") (class "Default")
      (node (ref "U1") (pin "126") (pinfunction "PG11_126") (pintype "passive"))
    )
    (net (code "125") (name "unconnected-(U1B-PG13-Pad128)") (class "Default")
      (node (ref "U1") (pin "128") (pinfunction "PG13_128") (pintype "passive"))
    )
    (net (code "126") (name "unconnected-(U1B-PG14-Pad129)") (class "Default")
      (node (ref "U1") (pin "129") (pinfunction "PG14_129") (pintype "passive"))
    )
    (net (code "127") (name "unconnected-(U1B-PG15-Pad132)") (class "Default")
      (node (ref "U1") (pin "132") (pinfunction "PG15_132") (pintype "passive"))
    )
  )
)
